# Sheet1.net
KiCad netlist of a schematic drawn in Altium Designer
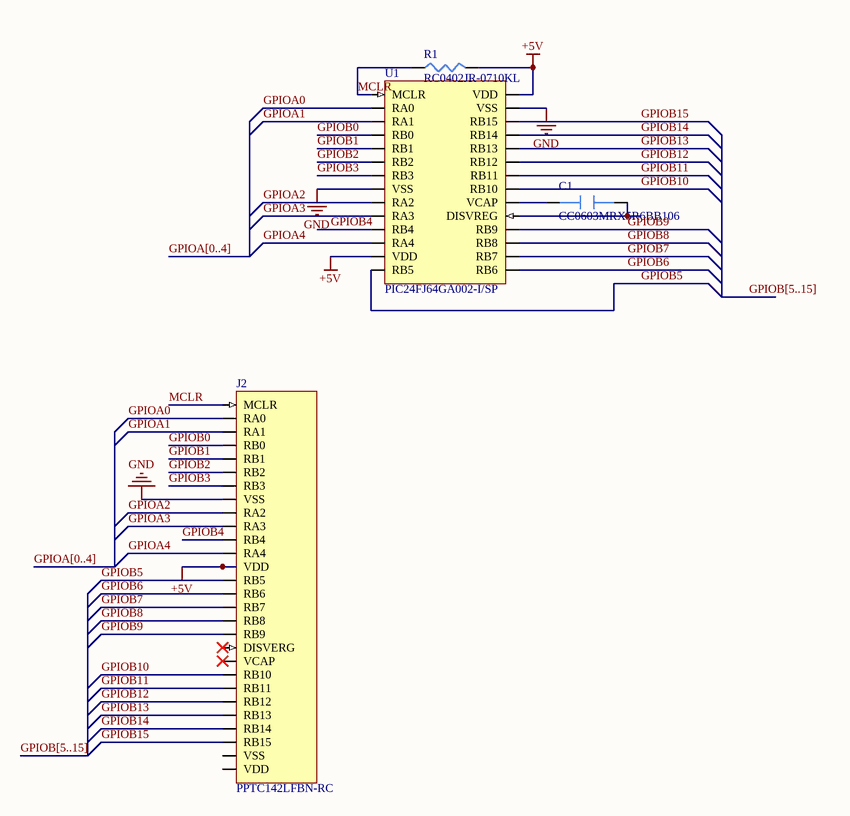
[diagram p0: Sheet1.SchDoc]

(export (version "E")
  (design (tool "Eeschema 10.0.6"))
  (components
    (comp (ref "C1")
      (value "CC0603MRX5R6BB106")
      (footprint "RC0402JR-0710KL")
      (fields (field (name "MANUFACTURER") "Yageo"))
      (libsource (lib "Schlib1") (part "CC0603MRX5R6BB106"))
    )
    (comp (ref "J2")
      (value "PPTC142LFBN-RC")
      (footprint "PPTC142LFBN-RC")
      (fields (field (name "MANUFACTURER") "Sullins"))
      (libsource (lib "Schlib1") (part "PPTC142LFBN-RC"))
    )
    (comp (ref "R1")
      (value "RC0402JR-0710KL")
      (footprint "RC0402JR-0710KL")
      (fields
        (field (name "MANUFACTURER") "Yageo")
        (field (name "TOLERANCE") "5%")
        (field (name "POWER") "62.5mW")
      )
      (libsource (lib "Schlib1") (part "RC0402JR-0710KL"))
    )
    (comp (ref "U1")
      (value "PIC24FJ64GA002-I/SP")
      (footprint "PIC24FJ64GA002-I/SP")
      (description "Microcontroller, 16-Bit, FLASH, PIC CPU, 32MHz, CMOS, PDIP28")
      (fields (field (name "MANUFACTURER") "Microchip"))
      (libsource (lib "Schlib1") (part "PIC24FJ64GA002-I/SP"))
    )
  )
  (nets
    (net (code "1") (name "+5V") (class "Default")
      (node (ref "J2") (pin "13") (pinfunction "VDD_13") (pintype "power_in"))
      (node (ref "R1") (pin "1") (pinfunction "1_1") (pintype "passive"))
      (node (ref "U1") (pin "13") (pinfunction "VDD_13") (pintype "power_in"))
      (node (ref "U1") (pin "28") (pinfunction "VDD_28") (pintype "power_in"))
    )
    (net (code "2") (name "/GPIOA0") (class "Default")
      (node (ref "J2") (pin "2") (pinfunction "RA0_2") (pintype "bidirectional"))
      (node (ref "U1") (pin "2") (pinfunction "RA0_2") (pintype "bidirectional"))
    )
    (net (code "3") (name "/GPIOA1") (class "Default")
      (node (ref "J2") (pin "3") (pinfunction "RA1_3") (pintype "bidirectional"))
      (node (ref "U1") (pin "3") (pinfunction "RA1_3") (pintype "bidirectional"))
    )
    (net (code "4") (name "/GPIOA2") (class "Default")
      (node (ref "J2") (pin "9") (pinfunction "RA2_9") (pintype "bidirectional"))
      (node (ref "U1") (pin "9") (pinfunction "RA2_9") (pintype "bidirectional"))
    )
    (net (code "5") (name "/GPIOA3") (class "Default")
      (node (ref "J2") (pin "10") (pinfunction "RA3_10") (pintype "bidirectional"))
      (node (ref "U1") (pin "10") (pinfunction "RA3_10") (pintype "bidirectional"))
    )
    (net (code "6") (name "/GPIOA4") (class "Default")
      (node (ref "J2") (pin "12") (pinfunction "RA4_12") (pintype "bidirectional"))
      (node (ref "U1") (pin "12") (pinfunction "RA4_12") (pintype "bidirectional"))
    )
    (net (code "8") (name "/GPIOB0") (class "Default")
      (node (ref "J2") (pin "4") (pinfunction "RB0_4") (pintype "bidirectional"))
      (node (ref "U1") (pin "4") (pinfunction "RB0_4") (pintype "bidirectional"))
    )
    (net (code "9") (name "/GPIOB1") (class "Default")
      (node (ref "J2") (pin "5") (pinfunction "RB1_5") (pintype "bidirectional"))
      (node (ref "U1") (pin "5") (pinfunction "RB1_5") (pintype "bidirectional"))
    )
    (net (code "10") (name "/GPIOB2") (class "Default")
      (node (ref "J2") (pin "6") (pinfunction "RB2_6") (pintype "bidirectional"))
      (node (ref "U1") (pin "6") (pinfunction "RB2_6") (pintype "bidirectional"))
    )
    (net (code "11") (name "/GPIOB3") (class "Default")
      (node (ref "J2") (pin "7") (pinfunction "RB3_7") (pintype "bidirectional"))
      (node (ref "U1") (pin "7") (pinfunction "RB3_7") (pintype "bidirectional"))
    )
    (net (code "12") (name "/GPIOB4") (class "Default")
      (node (ref "J2") (pin "11") (pinfunction "RB4_11") (pintype "bidirectional"))
      (node (ref "U1") (pin "11") (pinfunction "RB4_11") (pintype "bidirectional"))
    )
    (net (code "13") (name "/GPIOB5") (class "Default")
      (node (ref "J2") (pin "14") (pinfunction "RB5_14") (pintype "bidirectional"))
      (node (ref "U1") (pin "14") (pinfunction "RB5_14") (pintype "bidirectional"))
    )
    (net (code "14") (name "/GPIOB6") (class "Default")
      (node (ref "J2") (pin "15") (pinfunction "RB6_15") (pintype "bidirectional"))
      (node (ref "U1") (pin "15") (pinfunction "RB6_15") (pintype "bidirectional"))
    )
    (net (code "15") (name "/GPIOB7") (class "Default")
      (node (ref "J2") (pin "16") (pinfunction "RB7_16") (pintype "bidirectional"))
      (node (ref "U1") (pin "16") (pinfunction "RB7_16") (pintype "bidirectional"))
    )
    (net (code "16") (name "/GPIOB8") (class "Default")
      (node (ref "J2") (pin "17") (pinfunction "RB8_17") (pintype "bidirectional"))
      (node (ref "U1") (pin "17") (pinfunction "RB8_17") (pintype "bidirectional"))
    )
    (net (code "17") (name "/GPIOB9") (class "Default")
      (node (ref "J2") (pin "18") (pinfunction "RB9_18") (pintype "bidirectional"))
      (node (ref "U1") (pin "18") (pinfunction "RB9_18") (pintype "bidirectional"))
    )
    (net (code "18") (name "/GPIOB10") (class "Default")
      (node (ref "J2") (pin "21") (pinfunction "RB10_21") (pintype "bidirectional"))
      (node (ref "U1") (pin "21") (pinfunction "RB10_21") (pintype "bidirectional"))
    )
    (net (code "19") (name "/GPIOB11") (class "Default")
      (node (ref "J2") (pin "22") (pinfunction "RB11_22") (pintype "bidirectional"))
      (node (ref "U1") (pin "22") (pinfunction "RB11_22") (pintype "bidirectional"))
    )
    (net (code "20") (name "/GPIOB12") (class "Default")
      (node (ref "J2") (pin "23") (pinfunction "RB12_23") (pintype "bidirectional"))
      (node (ref "U1") (pin "23") (pinfunction "RB12_23") (pintype "bidirectional"))
    )
    (net (code "21") (name "/GPIOB13") (class "Default")
      (node (ref "J2") (pin "24") (pinfunction "RB13_24") (pintype "bidirectional"))
      (node (ref "U1") (pin "24") (pinfunction "RB13_24") (pintype "bidirectional"))
    )
    (net (code "22") (name "/GPIOB14") (class "Default")
      (node (ref "J2") (pin "25") (pinfunction "RB14_25") (pintype "bidirectional"))
      (node (ref "U1") (pin "25") (pinfunction "RB14_25") (pintype "bidirectional"))
    )
    (net (code "23") (name "/GPIOB15") (class "Default")
      (node (ref "J2") (pin "26") (pinfunction "RB15_26") (pintype "bidirectional"))
      (node (ref "U1") (pin "26") (pinfunction "RB15_26") (pintype "bidirectional"))
    )
    (net (code "25") (name "/MCLR") (class "Default")
      (node (ref "J2") (pin "1") (pinfunction "MCLR_1") (pintype "input"))
      (node (ref "R1") (pin "2") (pinfunction "2_2") (pintype "passive"))
      (node (ref "U1") (pin "1") (pinfunction "MCLR_1") (pintype "input"))
    )
    (net (code "26") (name "GND") (class "Default")
      (node (ref "J2") (pin "8") (pinfunction "VSS_8") (pintype "power_in"))
      (node (ref "U1") (pin "27") (pinfunction "VSS_27") (pintype "power_in"))
      (node (ref "U1") (pin "8") (pinfunction "VSS_8") (pintype "bidirectional"))
    )
    (net (code "27") (name "Net-(U1-DISVREG)") (class "Default")
      (node (ref "C1") (pin "2") (pinfunction "2_2") (pintype "passive"))
      (node (ref "U1") (pin "19") (pinfunction "DISVREG_19") (pintype "input"))
    )
    (net (code "28") (name "Net-(U1-VCAP)") (class "Default")
      (node (ref "C1") (pin "1") (pinfunction "1_1") (pintype "passive"))
      (node (ref "U1") (pin "20") (pinfunction "VCAP_20") (pintype "passive"))
    )
    (net (code "29") (name "unconnected-(J2-DISVERG-Pad19)") (class "Default")
      (node (ref "J2") (pin "19") (pinfunction "DISVERG_19") (pintype "input+no_connect"))
    )
    (net (code "30") (name "unconnected-(J2-VCAP-Pad20)") (class "Default")
      (node (ref "J2") (pin "20") (pinfunction "VCAP_20") (pintype "passive+no_connect"))
    )
    (net (code "31") (name "unconnected-(J2-VDD-Pad28)") (class "Default")
      (node (ref "J2") (pin "28") (pinfunction "VDD_28") (pintype "power_in"))
    )
    (net (code "32") (name "unconnected-(J2-VSS-Pad27)") (class "Default")
      (node (ref "J2") (pin "27") (pinfunction "VSS_27") (pintype "power_in"))
    )
  )
)
